# FC.net
KiCad netlist of a schematic drawn in Altium Designer
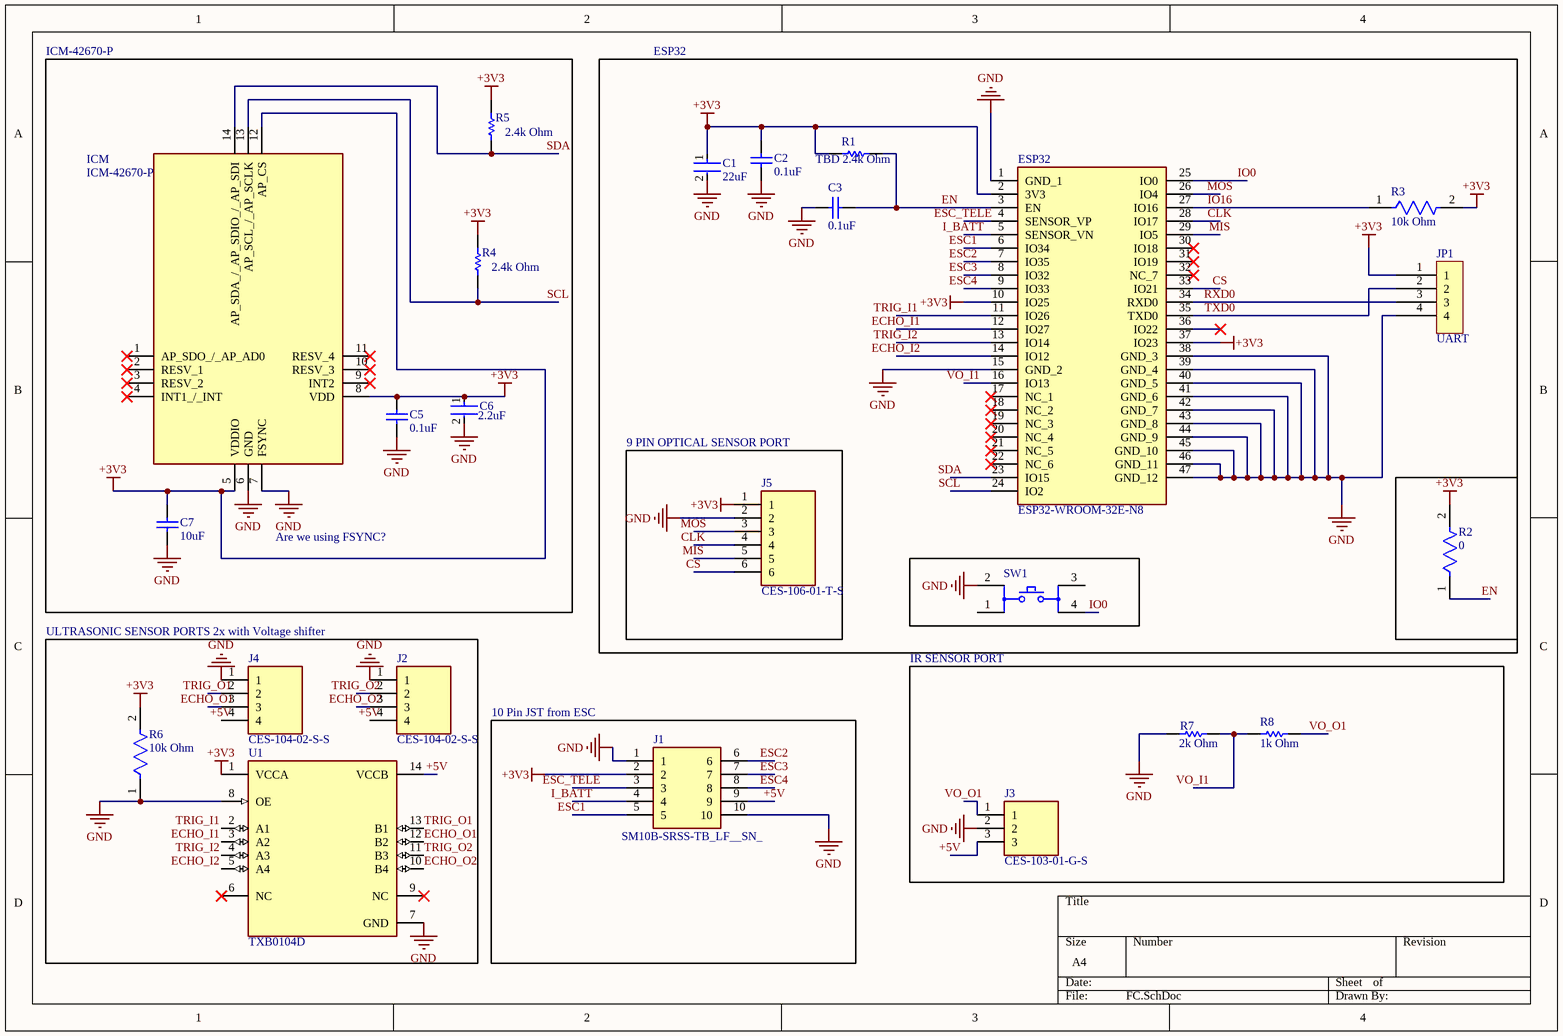
[diagram p0: FC.SchDoc]

(export (version "E")
  (design (tool "Eeschema 10.0.6"))
  (components
    (comp (ref "C1")
      (value "22uF")
      (footprint "FP-CL10-IPC_B")
      (description "Cap Ceramic 22uF 6.3V X5R ±20% Pad SMD 0603 +85°C T/R")
      (libsource (lib "Altium Content Vault") (part "b4654b650e69147ec39a6b967a45e02"))
    )
    (comp (ref "C2")
      (value "0.1uF")
      (footprint "CAPC0805(2012)145_M")
      (description "CAP 100nF 100V ±10% 0805 (2012 Metric) Thickness 1.45mm SMD")
      (fields (field (name "TOLERANCE") "Â±10%"))
      (libsource (lib "Altium Content Vault") (part "CAP"))
    )
    (comp (ref "C3")
      (value "0.1uF")
      (footprint "CAPC0805(2012)145_M")
      (description "CAP 100nF 100V ±10% 0805 (2012 Metric) Thickness 1.45mm SMD")
      (fields (field (name "TOLERANCE") "Â±10%"))
      (libsource (lib "Altium Content Vault") (part "CAP"))
    )
    (comp (ref "C5")
      (value "0.1uF")
      (footprint "CAPC0805(2012)145_M")
      (description "CAP 100nF 100V ±10% 0805 (2012 Metric) Thickness 1.45mm SMD")
      (fields (field (name "TOLERANCE") "Â±10%"))
      (libsource (lib "Altium Content Vault") (part "CAP"))
    )
    (comp (ref "C6")
      (value "2.2uF")
      (footprint "FP-CC0603-DA-MFG")
      (description "CC0603 2.2 uF X5R 10.00% 16 V")
      (fields
        (field (name "MANUFACTURER") "YAGEO")
        (field (name "MANUFACTURER PART NUMBER") "CC0603KPX5R7BB225")
      )
      (libsource (lib "Altium Content Vault") (part "11868f565c42a9108669ba33697ecf6"))
    )
    (comp (ref "C7")
      (value "10uF")
      (footprint "CAPC2013X140X50ML20T25")
      (fields
        (field (name "PART NUMBER") "08056D106KAT4A")
        (field (name "MANUFACTURER") "AVX Interconnect / Elco")
      )
      (libsource (lib "Altium Content Vault") (part "CAP"))
    )
    (comp (ref "ESP32")
      (value "ESP32-WROOM-32E-N8")
      (footprint "ESP32WROOM32EN8")
      (description "WiFi Modules - 802.11 SMD Module ESP32-WROOM-32E, ESP32-D0WD-V3, 8 MB SPI flash, PCB antenna")
      (fields (field (name "MOUSER PART NUMBER") "356-ESP32WRM32E164PH"))
      (libsource (lib "ESP32-WROOM-32E-N8") (part "ESP32-WROOM-32E-N8"))
    )
    (comp (ref "ICM")
      (value "ICM-42670-P")
      (footprint "ICM42670P")
      (description "Integrated Circuit")
      (fields (field (name "MOUSER PART NUMBER") "410-ICM-42670-P"))
      (libsource (lib "*") (part "ICM-42670-P"))
    )
    (comp (ref "J1")
      (value "SM10B-SRSS-TB_LF__SN_")
      (footprint "SM10B-SRSS-TB")
      (description "Connector")
      (fields
        (field (name "ARROW PART NUMBER") "SM10B-SRSS-TB(LF)(SN)")
        (field (name "MOUSER PART NUMBER") "306-SM10BSRSSTBLFSN")
      )
      (libsource (lib "Logan's Workspace") (part "SM10B-SRSS-TB_LF__SN_"))
    )
    (comp (ref "J2")
      (value "CES-104-02-S-S")
      (footprint "CES-104-XX-Y-S")
      (description "Connector")
      (libsource (lib "*") (part "CES-104-02-S-S"))
    )
    (comp (ref "J3")
      (value "CES-103-01-G-S")
      (footprint "CES-103-XX-Y-S")
      (description "Connector")
      (libsource (lib "*") (part "CES-103-01-G-S"))
    )
    (comp (ref "J4")
      (value "CES-104-02-S-S")
      (footprint "CES-104-XX-Y-S")
      (description "Connector")
      (libsource (lib "*") (part "CES-104-02-S-S"))
    )
    (comp (ref "J5")
      (value "CES-106-01-T-S")
      (footprint "CES-106-XX-Y-S")
      (description "Connector")
      (fields (field (name "MOUSER PART NUMBER") "200-CES10601TS"))
      (libsource (lib "*") (part "CES-106-01-T-S"))
    )
    (comp (ref "JP1")
      (value "UART")
      (footprint "HDR Male1~4 2.54mm")
      (description "CONN HEADER VERT 4POS 2.54MM")
      (fields
        (field (name "MANUFACTURER PART NUMBER") "68001-204HLF")
        (field (name "MANUFACTURER") "Amphenol FCI")
      )
      (libsource (lib "Logan's Workspace") (part "68001-204HLF"))
    )
    (comp (ref "R1")
      (value "TBD 2.4k Ohm")
      (footprint "RESC1608X55X30ML15T15")
      (fields (field (name "MANUFACTURER") "Panasonic") (field (name "PART NUMBER") "ERJ-3EKF2401V"))
      (libsource (lib "Altium Content Vault") (part "RES"))
    )
    (comp (ref "R2")
      (value "0")
      (footprint "FP-AC0603-IPC_A")
      (description "RES 10kΩ 5.00% 0.2W 0603")
      (libsource (lib "Altium Content Vault") (part "1029c3af85768c4190bb7ad29bc67b5"))
    )
    (comp (ref "R3")
      (value "10k Ohm")
      (footprint "FP-AC0603-IPC_A")
      (description "RES 10kΩ 5.00% 0.2W 0603")
      (libsource (lib "Altium Content Vault") (part "1029c3af85768c4190bb7ad29bc67b5"))
    )
    (comp (ref "R4")
      (value "2.4k Ohm")
      (footprint "RESC1608X55X30ML15T15")
      (fields (field (name "MANUFACTURER") "Panasonic") (field (name "PART NUMBER") "ERJ-3EKF2401V"))
      (libsource (lib "Altium Content Vault") (part "RES"))
    )
    (comp (ref "R5")
      (value "2.4k Ohm")
      (footprint "RESC1608X55X30ML15T15")
      (fields (field (name "MANUFACTURER") "Panasonic") (field (name "PART NUMBER") "ERJ-3EKF2401V"))
      (libsource (lib "Altium Content Vault") (part "RES"))
    )
    (comp (ref "R6")
      (value "10k Ohm")
      (footprint "FP-AC0603-IPC_A")
      (description "RES 10kΩ 5.00% 0.2W 0603")
      (libsource (lib "Altium Content Vault") (part "1029c3af85768c4190bb7ad29bc67b5"))
    )
    (comp (ref "R7")
      (value "2k Ohm")
      (footprint "RESC3116X65X40ML10T20")
      (fields (field (name "PART NUMBER") "RC1206FR-102KL") (field (name "MANUFACTURER") "Yageo"))
      (libsource (lib "Altium Content Vault") (part "RES"))
    )
    (comp (ref "R8")
      (value "1k Ohm")
      (footprint "RESC3116X65X40ML10T20")
      (fields (field (name "PART NUMBER") "RC1206JR-101KL") (field (name "MANUFACTURER") "Yageo"))
      (libsource (lib "Altium Content Vault") (part "RES"))
    )
    (comp (ref "SW1")
      (value "~")
      (footprint "FP-TL3301AF160QG-MFG")
      (description "SWITCH TACTILE SPST-NO 0.05A 12V")
      (libsource (lib "Altium Content Vault") (part "94cebf9f54af8bed749b87481745719"))
    )
    (comp (ref "U1")
      (value "TXB0104D")
      (footprint "FP-D0014A-IPC_A")
      (description "IC TRNSLTR BIDIRECTIONAL 14SOIC")
      (libsource (lib "Altium Content Vault") (part "3142e5fd72010881fdbc59e449d59ce"))
    )
  )
  (nets
    (net (code "1") (name "+3V3") (class "Default")
      (node (ref "C1") (pin "1") (pinfunction "1_1") (pintype "passive"))
      (node (ref "C2") (pin "2") (pinfunction "2_2") (pintype "passive"))
      (node (ref "C5") (pin "2") (pinfunction "2_2") (pintype "passive"))
      (node (ref "C6") (pin "1") (pinfunction "1_1") (pintype "passive"))
      (node (ref "C7") (pin "2") (pinfunction "2_2") (pintype "passive"))
      (node (ref "ESP32") (pin "10") (pinfunction "IO25_10") (pintype "passive"))
      (node (ref "ESP32") (pin "2") (pinfunction "3V3_2") (pintype "passive"))
      (node (ref "ESP32") (pin "37") (pinfunction "IO23_37") (pintype "passive"))
      (node (ref "ICM") (pin "12") (pinfunction "AP_CS_12") (pintype "passive"))
      (node (ref "ICM") (pin "5") (pinfunction "VDDIO_5") (pintype "passive"))
      (node (ref "ICM") (pin "8") (pinfunction "VDD_8") (pintype "passive"))
      (node (ref "J1") (pin "2") (pinfunction "2_2") (pintype "passive"))
      (node (ref "J5") (pin "1") (pinfunction "1_1") (pintype "passive"))
      (node (ref "JP1") (pin "1") (pinfunction "1_1") (pintype "passive"))
      (node (ref "R1") (pin "2") (pinfunction "2_2") (pintype "passive"))
      (node (ref "R2") (pin "2") (pinfunction "2_2") (pintype "passive"))
      (node (ref "R3") (pin "2") (pinfunction "2_2") (pintype "passive"))
      (node (ref "R4") (pin "2") (pinfunction "2_2") (pintype "passive"))
      (node (ref "R5") (pin "1") (pinfunction "1_1") (pintype "passive"))
      (node (ref "R6") (pin "2") (pinfunction "2_2") (pintype "passive"))
      (node (ref "U1") (pin "1") (pinfunction "VCCA_1") (pintype "power_in"))
    )
    (net (code "2") (name "/+5V") (class "Default")
      (node (ref "J1") (pin "9") (pinfunction "9_9") (pintype "passive"))
      (node (ref "J2") (pin "4") (pinfunction "4_4") (pintype "passive"))
      (node (ref "J3") (pin "3") (pinfunction "3_3") (pintype "passive"))
      (node (ref "J4") (pin "4") (pinfunction "4_4") (pintype "passive"))
      (node (ref "U1") (pin "14") (pinfunction "VCCB_14") (pintype "power_in"))
    )
    (net (code "3") (name "/CLK") (class "Default")
      (node (ref "ESP32") (pin "28") (pinfunction "IO17_28") (pintype "passive"))
      (node (ref "J5") (pin "4") (pinfunction "4_4") (pintype "passive"))
    )
    (net (code "4") (name "/CS") (class "Default")
      (node (ref "ESP32") (pin "33") (pinfunction "IO21_33") (pintype "passive"))
      (node (ref "J5") (pin "6") (pinfunction "6_6") (pintype "passive"))
    )
    (net (code "5") (name "/ECHO_I1") (class "Default")
      (node (ref "ESP32") (pin "12") (pinfunction "IO27_12") (pintype "passive"))
      (node (ref "U1") (pin "3") (pinfunction "A2_3") (pintype "bidirectional"))
    )
    (net (code "6") (name "/ECHO_I2") (class "Default")
      (node (ref "ESP32") (pin "14") (pinfunction "IO12_14") (pintype "passive"))
      (node (ref "U1") (pin "5") (pinfunction "A4_5") (pintype "bidirectional"))
    )
    (net (code "7") (name "/ECHO_O1") (class "Default")
      (node (ref "J4") (pin "3") (pinfunction "3_3") (pintype "passive"))
      (node (ref "U1") (pin "12") (pinfunction "B2_12") (pintype "bidirectional"))
    )
    (net (code "8") (name "/ECHO_O2") (class "Default")
      (node (ref "J2") (pin "3") (pinfunction "3_3") (pintype "passive"))
      (node (ref "U1") (pin "10") (pinfunction "B4_10") (pintype "bidirectional"))
    )
    (net (code "9") (name "/EN") (class "Default")
      (node (ref "C3") (pin "1") (pinfunction "1_1") (pintype "passive"))
      (node (ref "ESP32") (pin "3") (pinfunction "EN_3") (pintype "passive"))
      (node (ref "R1") (pin "1") (pinfunction "1_1") (pintype "passive"))
      (node (ref "R2") (pin "1") (pinfunction "1_1") (pintype "passive"))
    )
    (net (code "10") (name "/ESC1") (class "Default")
      (node (ref "ESP32") (pin "6") (pinfunction "IO34_6") (pintype "passive"))
      (node (ref "J1") (pin "5") (pinfunction "5_5") (pintype "passive"))
    )
    (net (code "11") (name "/ESC2") (class "Default")
      (node (ref "ESP32") (pin "7") (pinfunction "IO35_7") (pintype "passive"))
      (node (ref "J1") (pin "6") (pinfunction "6_6") (pintype "passive"))
    )
    (net (code "12") (name "/ESC3") (class "Default")
      (node (ref "ESP32") (pin "8") (pinfunction "IO32_8") (pintype "passive"))
      (node (ref "J1") (pin "7") (pinfunction "7_7") (pintype "passive"))
    )
    (net (code "13") (name "/ESC4") (class "Default")
      (node (ref "ESP32") (pin "9") (pinfunction "IO33_9") (pintype "passive"))
      (node (ref "J1") (pin "8") (pinfunction "8_8") (pintype "passive"))
    )
    (net (code "14") (name "/ESC_TELE") (class "Default")
      (node (ref "ESP32") (pin "4") (pinfunction "SENSOR_VP_4") (pintype "passive"))
      (node (ref "J1") (pin "3") (pinfunction "3_3") (pintype "passive"))
    )
    (net (code "15") (name "/IO0") (class "Default")
      (node (ref "ESP32") (pin "25") (pinfunction "IO0_25") (pintype "passive"))
      (node (ref "SW1") (pin "4") (pinfunction "4_4") (pintype "passive"))
    )
    (net (code "16") (name "/IO16") (class "Default")
      (node (ref "ESP32") (pin "27") (pinfunction "IO16_27") (pintype "passive"))
      (node (ref "R3") (pin "1") (pinfunction "1_1") (pintype "passive"))
    )
    (net (code "17") (name "/I_BATT") (class "Default")
      (node (ref "ESP32") (pin "5") (pinfunction "SENSOR_VN_5") (pintype "passive"))
      (node (ref "J1") (pin "4") (pinfunction "4_4") (pintype "passive"))
    )
    (net (code "18") (name "/MIS") (class "Default")
      (node (ref "ESP32") (pin "29") (pinfunction "IO5_29") (pintype "passive"))
      (node (ref "J5") (pin "5") (pinfunction "5_5") (pintype "passive"))
    )
    (net (code "19") (name "/MOS") (class "Default")
      (node (ref "ESP32") (pin "26") (pinfunction "IO4_26") (pintype "passive"))
      (node (ref "J5") (pin "3") (pinfunction "3_3") (pintype "passive"))
    )
    (net (code "20") (name "/RXD0") (class "Default")
      (node (ref "ESP32") (pin "34") (pinfunction "RXD0_34") (pintype "passive"))
      (node (ref "JP1") (pin "3") (pinfunction "3_3") (pintype "passive"))
    )
    (net (code "21") (name "/SCL") (class "Default")
      (node (ref "ESP32") (pin "24") (pinfunction "IO2_24") (pintype "passive"))
      (node (ref "ICM") (pin "13") (pinfunction "AP_SCL_/_AP_SCLK_13") (pintype "passive"))
      (node (ref "R4") (pin "1") (pinfunction "1_1") (pintype "passive"))
    )
    (net (code "22") (name "/SDA") (class "Default")
      (node (ref "ESP32") (pin "23") (pinfunction "IO15_23") (pintype "passive"))
      (node (ref "ICM") (pin "14") (pinfunction "AP_SDA_/_AP_SDIO_/_AP_SDI_14") (pintype "passive"))
      (node (ref "R5") (pin "2") (pinfunction "2_2") (pintype "passive"))
    )
    (net (code "23") (name "/TRIG_I1") (class "Default")
      (node (ref "ESP32") (pin "11") (pinfunction "IO26_11") (pintype "passive"))
      (node (ref "U1") (pin "2") (pinfunction "A1_2") (pintype "bidirectional"))
    )
    (net (code "24") (name "/TRIG_I2") (class "Default")
      (node (ref "ESP32") (pin "13") (pinfunction "IO14_13") (pintype "passive"))
      (node (ref "U1") (pin "4") (pinfunction "A3_4") (pintype "bidirectional"))
    )
    (net (code "25") (name "/TRIG_O1") (class "Default")
      (node (ref "J4") (pin "2") (pinfunction "2_2") (pintype "passive"))
      (node (ref "U1") (pin "13") (pinfunction "B1_13") (pintype "bidirectional"))
    )
    (net (code "26") (name "/TRIG_O2") (class "Default")
      (node (ref "J2") (pin "2") (pinfunction "2_2") (pintype "passive"))
      (node (ref "U1") (pin "11") (pinfunction "B3_11") (pintype "bidirectional"))
    )
    (net (code "27") (name "/TXD0") (class "Default")
      (node (ref "ESP32") (pin "35") (pinfunction "TXD0_35") (pintype "passive"))
      (node (ref "JP1") (pin "2") (pinfunction "2_2") (pintype "passive"))
    )
    (net (code "28") (name "/VO_I1") (class "Default")
      (node (ref "ESP32") (pin "16") (pinfunction "IO13_16") (pintype "passive"))
      (node (ref "R7") (pin "2") (pinfunction "2_2") (pintype "passive"))
      (node (ref "R8") (pin "1") (pinfunction "1_1") (pintype "passive"))
    )
    (net (code "29") (name "/VO_O1") (class "Default")
      (node (ref "J3") (pin "1") (pinfunction "1_1") (pintype "passive"))
      (node (ref "R8") (pin "2") (pinfunction "2_2") (pintype "passive"))
    )
    (net (code "30") (name "GND") (class "Default")
      (node (ref "C1") (pin "2") (pinfunction "2_2") (pintype "passive"))
      (node (ref "C2") (pin "1") (pinfunction "1_1") (pintype "passive"))
      (node (ref "C3") (pin "2") (pinfunction "2_2") (pintype "passive"))
      (node (ref "C5") (pin "1") (pinfunction "1_1") (pintype "passive"))
      (node (ref "C6") (pin "2") (pinfunction "2_2") (pintype "passive"))
      (node (ref "C7") (pin "1") (pinfunction "1_1") (pintype "passive"))
      (node (ref "ESP32") (pin "1") (pinfunction "GND_1_1") (pintype "passive"))
      (node (ref "ESP32") (pin "15") (pinfunction "GND_2_15") (pintype "passive"))
      (node (ref "ESP32") (pin "38") (pinfunction "GND_3_38") (pintype "passive"))
      (node (ref "ESP32") (pin "39") (pinfunction "GND_4_39") (pintype "passive"))
      (node (ref "ESP32") (pin "40") (pinfunction "GND_5_40") (pintype "passive"))
      (node (ref "ESP32") (pin "41") (pinfunction "GND_6_41") (pintype "passive"))
      (node (ref "ESP32") (pin "42") (pinfunction "GND_7_42") (pintype "passive"))
      (node (ref "ESP32") (pin "43") (pinfunction "GND_8_43") (pintype "passive"))
      (node (ref "ESP32") (pin "44") (pinfunction "GND_9_44") (pintype "passive"))
      (node (ref "ESP32") (pin "45") (pinfunction "GND_10_45") (pintype "passive"))
      (node (ref "ESP32") (pin "46") (pinfunction "GND_11_46") (pintype "passive"))
      (node (ref "ESP32") (pin "47") (pinfunction "GND_12_47") (pintype "passive"))
      (node (ref "ICM") (pin "6") (pinfunction "GND_6") (pintype "passive"))
      (node (ref "ICM") (pin "7") (pinfunction "FSYNC_7") (pintype "passive"))
      (node (ref "J1") (pin "1") (pinfunction "1_1") (pintype "passive"))
      (node (ref "J1") (pin "10") (pinfunction "10_10") (pintype "passive"))
      (node (ref "J2") (pin "1") (pinfunction "1_1") (pintype "passive"))
      (node (ref "J3") (pin "2") (pinfunction "2_2") (pintype "passive"))
      (node (ref "J4") (pin "1") (pinfunction "1_1") (pintype "passive"))
      (node (ref "J5") (pin "2") (pinfunction "2_2") (pintype "passive"))
      (node (ref "JP1") (pin "4") (pinfunction "4_4") (pintype "passive"))
      (node (ref "R6") (pin "1") (pinfunction "1_1") (pintype "passive"))
      (node (ref "R7") (pin "1") (pinfunction "1_1") (pintype "passive"))
      (node (ref "SW1") (pin "2") (pinfunction "2_2") (pintype "passive"))
      (node (ref "U1") (pin "7") (pinfunction "GND_7") (pintype "power_in"))
      (node (ref "U1") (pin "8") (pinfunction "OE_8") (pintype "input"))
    )
    (net (code "31") (name "unconnected-(ESP32-IO18-Pad30)") (class "Default")
      (node (ref "ESP32") (pin "30") (pinfunction "IO18_30") (pintype "passive+no_connect"))
    )
    (net (code "32") (name "unconnected-(ESP32-IO19-Pad31)") (class "Default")
      (node (ref "ESP32") (pin "31") (pinfunction "IO19_31") (pintype "passive+no_connect"))
    )
    (net (code "33") (name "unconnected-(ESP32-IO22-Pad36)") (class "Default")
      (node (ref "ESP32") (pin "36") (pinfunction "IO22_36") (pintype "passive+no_connect"))
    )
    (net (code "34") (name "unconnected-(ESP32-NC_1-Pad17)") (class "Default")
      (node (ref "ESP32") (pin "17") (pinfunction "NC_1_17") (pintype "passive+no_connect"))
    )
    (net (code "35") (name "unconnected-(ESP32-NC_2-Pad18)") (class "Default")
      (node (ref "ESP32") (pin "18") (pinfunction "NC_2_18") (pintype "passive+no_connect"))
    )
    (net (code "36") (name "unconnected-(ESP32-NC_3-Pad19)") (class "Default")
      (node (ref "ESP32") (pin "19") (pinfunction "NC_3_19") (pintype "passive+no_connect"))
    )
    (net (code "37") (name "unconnected-(ESP32-NC_4-Pad20)") (class "Default")
      (node (ref "ESP32") (pin "20") (pinfunction "NC_4_20") (pintype "passive+no_connect"))
    )
    (net (code "38") (name "unconnected-(ESP32-NC_5-Pad21)") (class "Default")
      (node (ref "ESP32") (pin "21") (pinfunction "NC_5_21") (pintype "passive+no_connect"))
    )
    (net (code "39") (name "unconnected-(ESP32-NC_6-Pad22)") (class "Default")
      (node (ref "ESP32") (pin "22") (pinfunction "NC_6_22") (pintype "passive+no_connect"))
    )
    (net (code "40") (name "unconnected-(ESP32-NC_7-Pad32)") (class "Default")
      (node (ref "ESP32") (pin "32") (pinfunction "NC_7_32") (pintype "passive+no_connect"))
    )
    (net (code "41") (name "unconnected-(ICM-AP_SDO_{slash}_AP_AD0-Pad1)") (class "Default")
      (node (ref "ICM") (pin "1") (pinfunction "AP_SDO_/_AP_AD0_1") (pintype "passive+no_connect"))
    )
    (net (code "42") (name "unconnected-(ICM-INT1_{slash}_INT-Pad4)") (class "Default")
      (node (ref "ICM") (pin "4") (pinfunction "INT1_/_INT_4") (pintype "passive+no_connect"))
    )
    (net (code "43") (name "unconnected-(ICM-INT2-Pad9)") (class "Default")
      (node (ref "ICM") (pin "9") (pinfunction "INT2_9") (pintype "passive+no_connect"))
    )
    (net (code "44") (name "unconnected-(ICM-RESV_1-Pad2)") (class "Default")
      (node (ref "ICM") (pin "2") (pinfunction "RESV_1_2") (pintype "passive+no_connect"))
    )
    (net (code "45") (name "unconnected-(ICM-RESV_2-Pad3)") (class "Default")
      (node (ref "ICM") (pin "3") (pinfunction "RESV_2_3") (pintype "passive+no_connect"))
    )
    (net (code "46") (name "unconnected-(ICM-RESV_3-Pad10)") (class "Default")
      (node (ref "ICM") (pin "10") (pinfunction "RESV_3_10") (pintype "passive+no_connect"))
    )
    (net (code "47") (name "unconnected-(ICM-RESV_4-Pad11)") (class "Default")
      (node (ref "ICM") (pin "11") (pinfunction "RESV_4_11") (pintype "passive+no_connect"))
    )
    (net (code "48") (name "unconnected-(SW1-Pad1)") (class "Default")
      (node (ref "SW1") (pin "1") (pinfunction "1_1") (pintype "passive"))
    )
    (net (code "49") (name "unconnected-(SW1-Pad3)") (class "Default")
      (node (ref "SW1") (pin "3") (pinfunction "3_3") (pintype "passive"))
    )
    (net (code "50") (name "unconnected-(U1-NC-Pad6)") (class "Default")
      (node (ref "U1") (pin "6") (pinfunction "NC_6") (pintype "passive+no_connect"))
    )
    (net (code "51") (name "unconnected-(U1-NC-Pad9)") (class "Default")
      (node (ref "U1") (pin "9") (pinfunction "NC_9") (pintype "passive+no_connect"))
    )
  )
)
